# NOPB.net
KiCad netlist of a schematic drawn in EAGLE
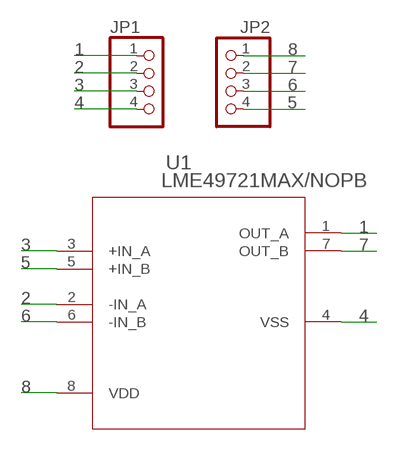
[diagram p0: schematic, sheet 1]

(export (version "E")
  (design (tool "Eeschema 10.0.6"))
  (components
    (comp (ref "JP1")
      (value "PINHD-1X4")
      (footprint "eagle-import:1X04")
      (libsource (lib "eagle-import") (part "PINHD-1X4"))
    )
    (comp (ref "JP2")
      (value "PINHD-1X4")
      (footprint "eagle-import:1X04")
      (libsource (lib "eagle-import") (part "PINHD-1X4"))
    )
    (comp (ref "U1")
      (value "LME49721MAX/NOPB")
      (footprint "eagle-import:M08A_TEX")
      (libsource (lib "eagle-import") (part "LME49721MAX/NOPB"))
    )
  )
  (nets
    (net (code "1") (name "/1") (class "Default")
      (node (ref "JP1") (pin "1") (pinfunction "1_1") (pintype "passive"))
      (node (ref "U1") (pin "1") (pinfunction "OUT_A_1") (pintype "output"))
    )
    (net (code "2") (name "/2") (class "Default")
      (node (ref "JP1") (pin "2") (pinfunction "2_2") (pintype "passive"))
      (node (ref "U1") (pin "2") (pinfunction "-IN_A_2") (pintype "input"))
    )
    (net (code "3") (name "/3") (class "Default")
      (node (ref "JP1") (pin "3") (pinfunction "3_3") (pintype "passive"))
      (node (ref "U1") (pin "3") (pinfunction "+IN_A_3") (pintype "input"))
    )
    (net (code "4") (name "/4") (class "Default")
      (node (ref "JP1") (pin "4") (pinfunction "4_4") (pintype "passive"))
      (node (ref "U1") (pin "4") (pinfunction "VSS_4") (pintype "power_in"))
    )
    (net (code "5") (name "/5") (class "Default")
      (node (ref "JP2") (pin "4") (pinfunction "4_4") (pintype "passive"))
      (node (ref "U1") (pin "5") (pinfunction "+IN_B_5") (pintype "input"))
    )
    (net (code "6") (name "/6") (class "Default")
      (node (ref "JP2") (pin "3") (pinfunction "3_3") (pintype "passive"))
      (node (ref "U1") (pin "6") (pinfunction "-IN_B_6") (pintype "input"))
    )
    (net (code "7") (name "/7") (class "Default")
      (node (ref "JP2") (pin "2") (pinfunction "2_2") (pintype "passive"))
      (node (ref "U1") (pin "7") (pinfunction "OUT_B_7") (pintype "output"))
    )
    (net (code "8") (name "/8") (class "Default")
      (node (ref "JP2") (pin "1") (pinfunction "1_1") (pintype "passive"))
      (node (ref "U1") (pin "8") (pinfunction "VDD_8") (pintype "power_in"))
    )
  )
)
